# ASURA7200.net
KiCad netlist of a schematic drawn in EAGLE
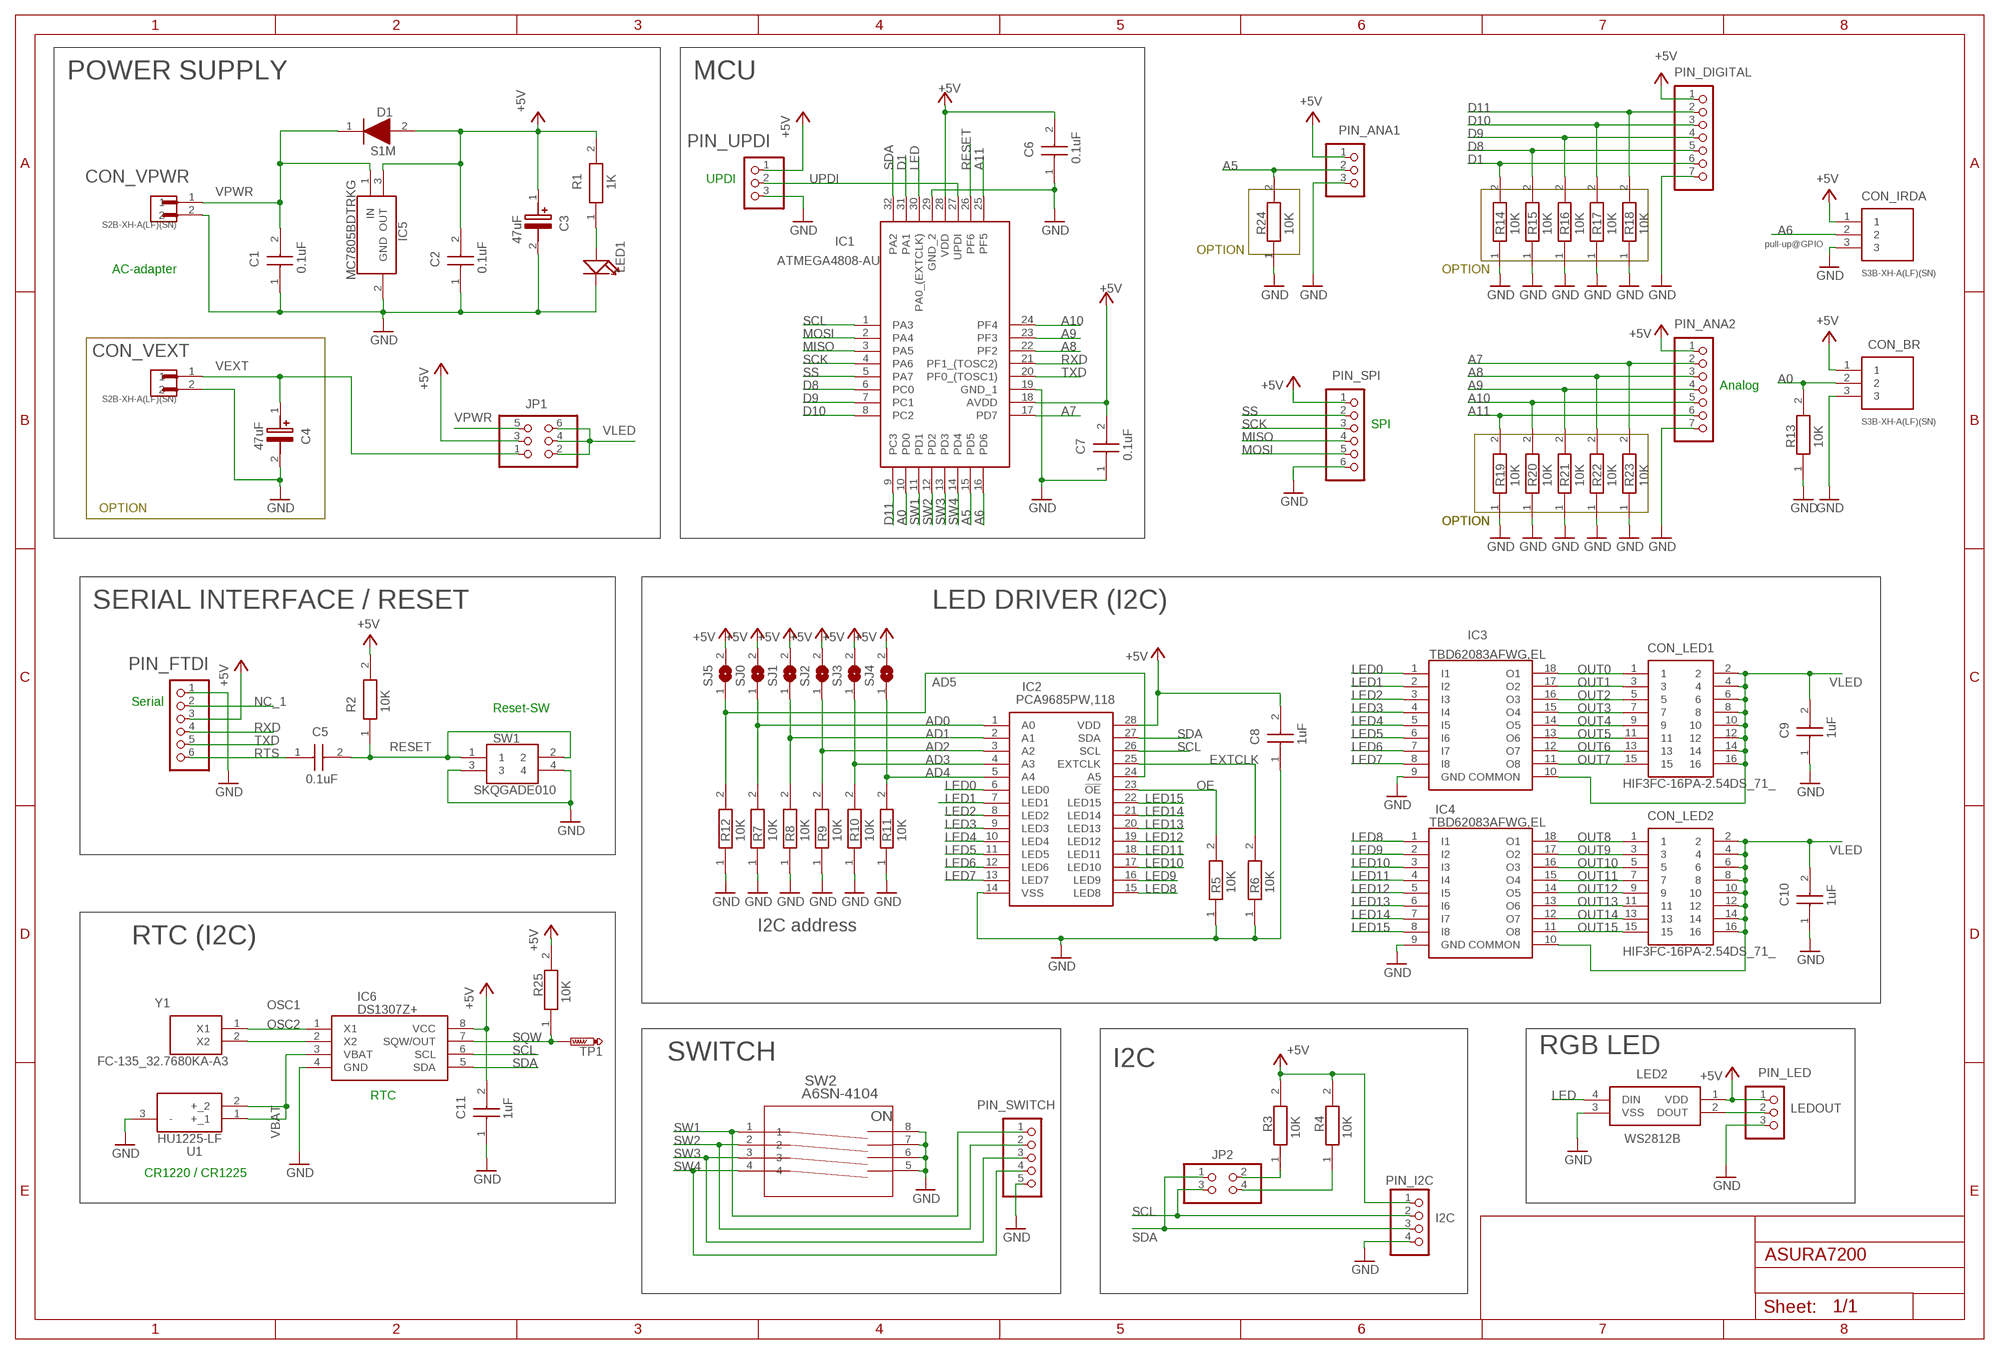
[diagram p0: schematic, sheet 1]

(export (version "E")
  (design (tool "Eeschema 10.0.6"))
  (components
    (comp (ref "C1")
      (value "CC0603KRX7R9BB104")
      (footprint "eagle-import:CAPC1608X90N")
      (fields (field (name "MOUSER_PART_NUMBER") "603-CC603KRX7R9BB104") (field (name "C") "0.1uF"))
      (libsource (lib "eagle-import") (part "CC0603KRX7R9BB104_31382856_CC0603KRX7R9BB104"))
    )
    (comp (ref "C2")
      (value "CC0603KRX7R8BB105")
      (footprint "eagle-import:CAPC1608X90N")
      (fields (field (name "MOUSER_PART_NUMBER") "603-CC603KRX7R8BB105") (field (name "C") "0.1uF"))
      (libsource (lib "eagle-import") (part "CC0603KRX7R8BB105"))
    )
    (comp (ref "C3")
      (value "UUD1H470MCL1GS")
      (footprint "eagle-import:CAPAE660X800N")
      (fields (field (name "RS_PART_NUMBER") "1677902") (field (name "C") "47uF"))
      (libsource (lib "eagle-import") (part "UUD1H470MCL1GS"))
    )
    (comp (ref "C4")
      (value "UUD1H470MCL1GS")
      (footprint "eagle-import:CAPAE660X800N")
      (fields (field (name "RS_PART_NUMBER") "1677902") (field (name "C") "47uF"))
      (libsource (lib "eagle-import") (part "UUD1H470MCL1GS"))
    )
    (comp (ref "C5")
      (value "CC0603KRX7R8BB105")
      (footprint "eagle-import:CAPC1608X90N")
      (fields (field (name "MOUSER_PART_NUMBER") "603-CC603KRX7R8BB105") (field (name "C") "0.1uF"))
      (libsource (lib "eagle-import") (part "CC0603KRX7R8BB105"))
    )
    (comp (ref "C6")
      (value "CC0603KRX7R8BB105")
      (footprint "eagle-import:CAPC1608X90N")
      (fields (field (name "MOUSER_PART_NUMBER") "603-CC603KRX7R8BB105") (field (name "C") "0.1uF"))
      (libsource (lib "eagle-import") (part "CC0603KRX7R8BB105"))
    )
    (comp (ref "C7")
      (value "CC0603KRX7R8BB105")
      (footprint "eagle-import:CAPC1608X90N")
      (fields (field (name "MOUSER_PART_NUMBER") "603-CC603KRX7R8BB105") (field (name "C") "0.1uF"))
      (libsource (lib "eagle-import") (part "CC0603KRX7R8BB105"))
    )
    (comp (ref "C8")
      (value "CC0603KRX7R9BB104")
      (footprint "eagle-import:CAPC1608X90N")
      (fields (field (name "MOUSER_PART_NUMBER") "603-CC603KRX7R9BB104") (field (name "C") "1uF"))
      (libsource (lib "eagle-import") (part "CC0603KRX7R9BB104"))
    )
    (comp (ref "C9")
      (value "CC0603KRX7R9BB104")
      (footprint "eagle-import:CAPC1608X90N")
      (fields (field (name "MOUSER_PART_NUMBER") "603-CC603KRX7R9BB104") (field (name "C") "1uF"))
      (libsource (lib "eagle-import") (part "CC0603KRX7R9BB104"))
    )
    (comp (ref "C10")
      (value "CC0603KRX7R9BB104")
      (footprint "eagle-import:CAPC1608X90N")
      (fields (field (name "MOUSER_PART_NUMBER") "603-CC603KRX7R9BB104") (field (name "C") "1uF"))
      (libsource (lib "eagle-import") (part "CC0603KRX7R9BB104"))
    )
    (comp (ref "C11")
      (value "CC0603KRX7R8BB105")
      (footprint "eagle-import:CAPC1608X90N")
      (fields (field (name "MOUSER_PART_NUMBER") "603-CC603KRX7R8BB105") (field (name "C") "1uF"))
      (libsource (lib "eagle-import") (part "CC0603KRX7R8BB105"))
    )
    (comp (ref "CON_BR")
      (value "S3B-XH-A(LF)(SN)")
      (footprint "eagle-import:JST_S3B-XH-A(LF)(SN)")
      (fields (field (name "DIGI-KEY_PART_NUMBER") "455-2250-ND") (field (name "MF") "JST Sales"))
      (libsource (lib "eagle-import") (part "S3B-XH-A(LF)(SN)"))
    )
    (comp (ref "CON_IRDA")
      (value "S3B-XH-A(LF)(SN)")
      (footprint "eagle-import:JST_S3B-XH-A(LF)(SN)")
      (fields (field (name "DIGI-KEY_PART_NUMBER") "455-2250-ND") (field (name "MF") "JST Sales"))
      (libsource (lib "eagle-import") (part "S3B-XH-A(LF)(SN)"))
    )
    (comp (ref "CON_LED1")
      (value "HIF3FC-16PA-2.54DS_71_")
      (footprint "eagle-import:SHDRRA16W69P254X254_2X8_2782X8")
      (fields
        (field (name "MANUFACTURER_PART_NUMBER") "HIF3FC-16PA-2.54DS(71)")
        (field (name "MOUSER_PART_NUMBER") "798-HIF3FC16PA254DS1")
      )
      (libsource (lib "eagle-import") (part "HIF3FC-16PA-2.54DS_71_"))
    )
    (comp (ref "CON_LED2")
      (value "HIF3FC-16PA-2.54DS_71_")
      (footprint "eagle-import:SHDRRA16W69P254X254_2X8_2782X8")
      (fields
        (field (name "MANUFACTURER_PART_NUMBER") "HIF3FC-16PA-2.54DS(71)")
        (field (name "MOUSER_PART_NUMBER") "798-HIF3FC16PA254DS1")
      )
      (libsource (lib "eagle-import") (part "HIF3FC-16PA-2.54DS_71_"))
    )
    (comp (ref "CON_VEXT")
      (value "S2B-XH-A(LF)(SN)")
      (footprint "eagle-import:JST_S2B-XH-A(LF)(SN)")
      (fields (field (name "MF") "JST Sales"))
      (libsource (lib "eagle-import") (part "S2B-XH-A(LF)(SN)"))
    )
    (comp (ref "CON_VPWR")
      (value "S2B-XH-A(LF)(SN)")
      (footprint "eagle-import:JST_S2B-XH-A(LF)(SN)")
      (fields (field (name "MF") "JST Sales"))
      (libsource (lib "eagle-import") (part "S2B-XH-A(LF)(SN)"))
    )
    (comp (ref "D1")
      (value "S1M")
      (footprint "eagle-import:DIOM5227X270N")
      (fields (field (name "RS_PART_NUMBER") "6708836"))
      (libsource (lib "eagle-import") (part "S1M"))
    )
    (comp (ref "IC1")
      (value "ATMEGA4808-AU")
      (footprint "eagle-import:QFP80P900X900X120-32N")
      (fields (field (name "MOUSER_PART_NUMBER") "556-ATMEGA4808-AU"))
      (libsource (lib "eagle-import") (part "ATMEGA4808-AU"))
    )
    (comp (ref "IC2")
      (value "PCA9685PW,118")
      (footprint "eagle-import:SOP65P640X110-28N")
      (fields (field (name "MOUSER_PART_NUMBER") "771-PCA9685PW,118"))
      (libsource (lib "eagle-import") (part "PCA9685PW,118"))
    )
    (comp (ref "IC3")
      (value "TBD62083AFWG,EL")
      (footprint "eagle-import:SOIC127P1032X285-18N")
      (fields (field (name "MOUSER_PART_NUMBER") "757-TBD62083AFWGEL"))
      (libsource (lib "eagle-import") (part "TBD62083AFWG,EL"))
    )
    (comp (ref "IC4")
      (value "TBD62083AFWG,EL")
      (footprint "eagle-import:SOIC127P1032X285-18N")
      (fields (field (name "MOUSER_PART_NUMBER") "757-TBD62083AFWGEL"))
      (libsource (lib "eagle-import") (part "TBD62083AFWG,EL"))
    )
    (comp (ref "IC5")
      (value "MC7805BDTRKG")
      (footprint "eagle-import:LM317MADTRKG")
      (fields (field (name "MOUSER_PART_NUMBER") "863-MC7805BDTRKG"))
      (libsource (lib "eagle-import") (part "MC7805BDTRKG"))
    )
    (comp (ref "IC6")
      (value "DS1307Z+")
      (footprint "eagle-import:SOIC127P600X175-8N")
      (fields (field (name "MOUSER_PART_NUMBER") "700-DS1307Z"))
      (libsource (lib "eagle-import") (part "DS1307Z+"))
    )
    (comp (ref "JP1")
      (value "PINHD-2X3")
      (footprint "eagle-import:2X03")
      (libsource (lib "eagle-import") (part "PINHD-2X3"))
    )
    (comp (ref "JP2")
      (value "PINHD-2X2")
      (footprint "eagle-import:2X02")
      (libsource (lib "eagle-import") (part "PINHD-2X2"))
    )
    (comp (ref "LED1")
      (value "SMD-LED-CLEAR-GREEN(0603)")
      (footprint "eagle-import:LED-0603")
      (fields (field (name "MF") "Everlight") (field (name "MP") "19-217/G7C-AN1P2/3T"))
      (libsource (lib "eagle-import") (part "SMD-LED-CLEAR-GREEN(0603)"))
    )
    (comp (ref "LED2")
      (value "WS2812B")
      (footprint "eagle-import:WS2812B")
      (libsource (lib "eagle-import") (part "WS2812B"))
    )
    (comp (ref "PIN_ANA1")
      (value "PINHD-1X3")
      (footprint "eagle-import:1X03")
      (libsource (lib "eagle-import") (part "PINHD-1X3"))
    )
    (comp (ref "PIN_ANA2")
      (value "PINHD-1X7")
      (footprint "eagle-import:1X07")
      (libsource (lib "eagle-import") (part "PINHD-1X7"))
    )
    (comp (ref "PIN_DIGITAL")
      (value "PINHD-1X7")
      (footprint "eagle-import:1X07")
      (libsource (lib "eagle-import") (part "PINHD-1X7"))
    )
    (comp (ref "PIN_FTDI")
      (value "PINHD-1X6/90")
      (footprint "eagle-import:1X06_90")
      (libsource (lib "eagle-import") (part "PINHD-1X6/90"))
    )
    (comp (ref "PIN_I2C")
      (value "PINHD-1X4")
      (footprint "eagle-import:1X04")
      (libsource (lib "eagle-import") (part "PINHD-1X4"))
    )
    (comp (ref "PIN_LED")
      (value "PINHD-1X3")
      (footprint "eagle-import:1X03")
      (libsource (lib "eagle-import") (part "PINHD-1X3"))
    )
    (comp (ref "PIN_SPI")
      (value "PINHD-1X6")
      (footprint "eagle-import:1X06")
      (libsource (lib "eagle-import") (part "PINHD-1X6"))
    )
    (comp (ref "PIN_SWITCH")
      (value "PINHD-1X5")
      (footprint "eagle-import:1X05")
      (libsource (lib "eagle-import") (part "PINHD-1X5"))
    )
    (comp (ref "PIN_UPDI")
      (value "PINHD-1X3")
      (footprint "eagle-import:1X03")
      (libsource (lib "eagle-import") (part "PINHD-1X3"))
    )
    (comp (ref "R1")
      (value "RC0603JR-071KL")
      (footprint "eagle-import:RESC1608X55N")
      (fields (field (name "MOUSER_PART_NUMBER") "603-RC0603JR-071KL") (field (name "R") "1K"))
      (libsource (lib "eagle-import") (part "RC0603JR-071KL"))
    )
    (comp (ref "R2")
      (value "RC0603JR-0710KL")
      (footprint "eagle-import:RESC1608X55N")
      (fields (field (name "MOUSER_PART_NUMBER") "603-RC0603JR-0710KL") (field (name "R") "10K"))
      (libsource (lib "eagle-import") (part "RC0603JR-0710KL"))
    )
    (comp (ref "R3")
      (value "RC0603JR-0710KL")
      (footprint "eagle-import:RESC1608X55N")
      (fields (field (name "MOUSER_PART_NUMBER") "603-RC0603JR-0710KL") (field (name "R") "10K"))
      (libsource (lib "eagle-import") (part "RC0603JR-0710KL"))
    )
    (comp (ref "R4")
      (value "RC0603JR-0710KL")
      (footprint "eagle-import:RESC1608X55N")
      (fields (field (name "MOUSER_PART_NUMBER") "603-RC0603JR-0710KL") (field (name "R") "10K"))
      (libsource (lib "eagle-import") (part "RC0603JR-0710KL"))
    )
    (comp (ref "R5")
      (value "RC0603JR-0710KL")
      (footprint "eagle-import:RESC1608X55N")
      (fields (field (name "MOUSER_PART_NUMBER") "603-RC0603JR-0710KL") (field (name "R") "10K"))
      (libsource (lib "eagle-import") (part "RC0603JR-0710KL"))
    )
    (comp (ref "R6")
      (value "RC0603JR-0710KL")
      (footprint "eagle-import:RESC1608X55N")
      (fields (field (name "MOUSER_PART_NUMBER") "603-RC0603JR-0710KL") (field (name "R") "10K"))
      (libsource (lib "eagle-import") (part "RC0603JR-0710KL"))
    )
    (comp (ref "R7")
      (value "RC0603JR-0710KL")
      (footprint "eagle-import:RESC1608X55N")
      (fields (field (name "MOUSER_PART_NUMBER") "603-RC0603JR-0710KL") (field (name "R") "10K"))
      (libsource (lib "eagle-import") (part "RC0603JR-0710KL"))
    )
    (comp (ref "R8")
      (value "RC0603JR-0710KL")
      (footprint "eagle-import:RESC1608X55N")
      (fields (field (name "MOUSER_PART_NUMBER") "603-RC0603JR-0710KL") (field (name "R") "10K"))
      (libsource (lib "eagle-import") (part "RC0603JR-0710KL"))
    )
    (comp (ref "R9")
      (value "RC0603JR-0710KL")
      (footprint "eagle-import:RESC1608X55N")
      (fields (field (name "MOUSER_PART_NUMBER") "603-RC0603JR-0710KL") (field (name "R") "10K"))
      (libsource (lib "eagle-import") (part "RC0603JR-0710KL"))
    )
    (comp (ref "R10")
      (value "RC0603JR-0710KL")
      (footprint "eagle-import:RESC1608X55N")
      (fields (field (name "MOUSER_PART_NUMBER") "603-RC0603JR-0710KL") (field (name "R") "10K"))
      (libsource (lib "eagle-import") (part "RC0603JR-0710KL"))
    )
    (comp (ref "R11")
      (value "RC0603JR-0710KL")
      (footprint "eagle-import:RESC1608X55N")
      (fields (field (name "MOUSER_PART_NUMBER") "603-RC0603JR-0710KL") (field (name "R") "10K"))
      (libsource (lib "eagle-import") (part "RC0603JR-0710KL"))
    )
    (comp (ref "R12")
      (value "RC0603JR-0710KL")
      (footprint "eagle-import:RESC1608X55N")
      (fields (field (name "MOUSER_PART_NUMBER") "603-RC0603JR-0710KL") (field (name "R") "10K"))
      (libsource (lib "eagle-import") (part "RC0603JR-0710KL"))
    )
    (comp (ref "R13")
      (value "RC0603JR-0710KL")
      (footprint "eagle-import:RESC1608X55N")
      (fields (field (name "MOUSER_PART_NUMBER") "603-RC0603JR-0710KL") (field (name "R") "10K"))
      (libsource (lib "eagle-import") (part "RC0603JR-0710KL"))
    )
    (comp (ref "R14")
      (value "RC0603JR-0710KL")
      (footprint "eagle-import:RESC1608X55N")
      (fields (field (name "MOUSER_PART_NUMBER") "603-RC0603JR-0710KL") (field (name "R") "10K"))
      (libsource (lib "eagle-import") (part "RC0603JR-0710KL"))
    )
    (comp (ref "R15")
      (value "RC0603JR-0710KL")
      (footprint "eagle-import:RESC1608X55N")
      (fields (field (name "MOUSER_PART_NUMBER") "603-RC0603JR-0710KL") (field (name "R") "10K"))
      (libsource (lib "eagle-import") (part "RC0603JR-0710KL"))
    )
    (comp (ref "R16")
      (value "RC0603JR-0710KL")
      (footprint "eagle-import:RESC1608X55N")
      (fields (field (name "MOUSER_PART_NUMBER") "603-RC0603JR-0710KL") (field (name "R") "10K"))
      (libsource (lib "eagle-import") (part "RC0603JR-0710KL"))
    )
    (comp (ref "R17")
      (value "RC0603JR-0710KL")
      (footprint "eagle-import:RESC1608X55N")
      (fields (field (name "MOUSER_PART_NUMBER") "603-RC0603JR-0710KL") (field (name "R") "10K"))
      (libsource (lib "eagle-import") (part "RC0603JR-0710KL"))
    )
    (comp (ref "R18")
      (value "RC0603JR-0710KL")
      (footprint "eagle-import:RESC1608X55N")
      (fields (field (name "MOUSER_PART_NUMBER") "603-RC0603JR-0710KL") (field (name "R") "10K"))
      (libsource (lib "eagle-import") (part "RC0603JR-0710KL"))
    )
    (comp (ref "R19")
      (value "RC0603JR-0710KL")
      (footprint "eagle-import:RESC1608X55N")
      (fields (field (name "MOUSER_PART_NUMBER") "603-RC0603JR-0710KL") (field (name "R") "10K"))
      (libsource (lib "eagle-import") (part "RC0603JR-0710KL"))
    )
    (comp (ref "R20")
      (value "RC0603JR-0710KL")
      (footprint "eagle-import:RESC1608X55N")
      (fields (field (name "MOUSER_PART_NUMBER") "603-RC0603JR-0710KL") (field (name "R") "10K"))
      (libsource (lib "eagle-import") (part "RC0603JR-0710KL"))
    )
    (comp (ref "R21")
      (value "RC0603JR-0710KL")
      (footprint "eagle-import:RESC1608X55N")
      (fields (field (name "MOUSER_PART_NUMBER") "603-RC0603JR-0710KL") (field (name "R") "10K"))
      (libsource (lib "eagle-import") (part "RC0603JR-0710KL"))
    )
    (comp (ref "R22")
      (value "RC0603JR-0710KL")
      (footprint "eagle-import:RESC1608X55N")
      (fields (field (name "MOUSER_PART_NUMBER") "603-RC0603JR-0710KL") (field (name "R") "10K"))
      (libsource (lib "eagle-import") (part "RC0603JR-0710KL"))
    )
    (comp (ref "R23")
      (value "RC0603JR-0710KL")
      (footprint "eagle-import:RESC1608X55N")
      (fields (field (name "MOUSER_PART_NUMBER") "603-RC0603JR-0710KL") (field (name "R") "10K"))
      (libsource (lib "eagle-import") (part "RC0603JR-0710KL"))
    )
    (comp (ref "R24")
      (value "RC0603JR-0710KL")
      (footprint "eagle-import:RESC1608X55N")
      (fields (field (name "MOUSER_PART_NUMBER") "603-RC0603JR-0710KL") (field (name "R") "10K"))
      (libsource (lib "eagle-import") (part "RC0603JR-0710KL"))
    )
    (comp (ref "R25")
      (value "RC0603JR-0710KL")
      (footprint "eagle-import:RESC1608X55N")
      (fields (field (name "MOUSER_PART_NUMBER") "603-RC0603JR-0710KL") (field (name "R") "10K"))
      (libsource (lib "eagle-import") (part "RC0603JR-0710KL"))
    )
    (comp (ref "SJ0") (value "SJ") (footprint "eagle-import:SJ") (libsource (lib "eagle-import") (part "SJ")))
    (comp (ref "SJ1") (value "SJ") (footprint "eagle-import:SJ") (libsource (lib "eagle-import") (part "SJ")))
    (comp (ref "SJ2") (value "SJ") (footprint "eagle-import:SJ") (libsource (lib "eagle-import") (part "SJ")))
    (comp (ref "SJ3") (value "SJ") (footprint "eagle-import:SJ") (libsource (lib "eagle-import") (part "SJ")))
    (comp (ref "SJ4") (value "SJ") (footprint "eagle-import:SJ") (libsource (lib "eagle-import") (part "SJ")))
    (comp (ref "SJ5") (value "SJ") (footprint "eagle-import:SJ") (libsource (lib "eagle-import") (part "SJ")))
    (comp (ref "SW1")
      (value "SKQGADE010")
      (footprint "eagle-import:SKQGAKE010")
      (fields (field (name "MOUSER_PART_NUMBER") "688-SKQGAD"))
      (libsource (lib "eagle-import") (part "SKQGADE010"))
    )
    (comp (ref "SW2")
      (value "A6SN-4104")
      (footprint "eagle-import:SW_A6SN-4104_OMR")
      (fields (field (name "COPYRIGHT") "Copyright (C) 2018 Accelerated Designs. All rights reserved"))
      (libsource (lib "eagle-import") (part "A6SN-4104"))
    )
    (comp (ref "TP1")
      (value "PTR1PAD1-13")
      (footprint "eagle-import:P1-13")
      (libsource (lib "eagle-import") (part "PTR1PAD1-13"))
    )
    (comp (ref "U1")
      (value "HU1225-LF")
      (footprint "eagle-import:HU1225LF")
      (fields (field (name "MOUSER_PART_NUMBER") "614-HU1225-LF"))
      (libsource (lib "eagle-import") (part "HU1225-LF"))
    )
    (comp (ref "Y1")
      (value "FC-135_32.7680KA-A3")
      (footprint "eagle-import:FC135327680KAA3")
      (fields
        (field (name "MANUFACTURER_PART_NUMBER") "FC-135 32.7680KA-A3")
        (field (name "MOUSER_PART_NUMBER") "732-FC135-32.76KAA3")
      )
      (libsource (lib "eagle-import") (part "FC-135_32.7680KA-A3"))
    )
  )
  (nets
    (net (code "1") (name "+5V") (class "Default")
      (node (ref "C11") (pin "2") (pinfunction "2_2") (pintype "bidirectional"))
      (node (ref "C2") (pin "2") (pinfunction "2_2") (pintype "bidirectional"))
      (node (ref "C3") (pin "1") (pinfunction "+_1") (pintype "bidirectional"))
      (node (ref "C6") (pin "2") (pinfunction "2_2") (pintype "bidirectional"))
      (node (ref "C7") (pin "2") (pinfunction "2_2") (pintype "bidirectional"))
      (node (ref "C8") (pin "2") (pinfunction "2_2") (pintype "bidirectional"))
      (node (ref "CON_BR") (pin "1") (pinfunction "1_1") (pintype "passive"))
      (node (ref "CON_IRDA") (pin "1") (pinfunction "1_1") (pintype "passive"))
      (node (ref "D1") (pin "2") (pinfunction "A_2") (pintype "bidirectional"))
      (node (ref "IC1") (pin "18") (pinfunction "AVDD_18") (pintype "bidirectional"))
      (node (ref "IC1") (pin "28") (pinfunction "VDD_28") (pintype "bidirectional"))
      (node (ref "IC2") (pin "28") (pinfunction "VDD_28") (pintype "bidirectional"))
      (node (ref "IC5") (pin "3") (pinfunction "OUT_3") (pintype "bidirectional"))
      (node (ref "IC6") (pin "8") (pinfunction "VCC_8") (pintype "bidirectional"))
      (node (ref "JP1") (pin "3") (pinfunction "3_3") (pintype "passive"))
      (node (ref "LED2") (pin "1") (pinfunction "VDD_1") (pintype "power_in"))
      (node (ref "PIN_ANA1") (pin "1") (pinfunction "1_1") (pintype "passive"))
      (node (ref "PIN_ANA2") (pin "1") (pinfunction "1_1") (pintype "passive"))
      (node (ref "PIN_DIGITAL") (pin "1") (pinfunction "1_1") (pintype "passive"))
      (node (ref "PIN_FTDI") (pin "3") (pinfunction "3_3") (pintype "passive"))
      (node (ref "PIN_I2C") (pin "1") (pinfunction "1_1") (pintype "passive"))
      (node (ref "PIN_LED") (pin "1") (pinfunction "1_1") (pintype "passive"))
      (node (ref "PIN_SPI") (pin "1") (pinfunction "1_1") (pintype "passive"))
      (node (ref "PIN_UPDI") (pin "1") (pinfunction "1_1") (pintype "passive"))
      (node (ref "R1") (pin "2") (pinfunction "2_2") (pintype "bidirectional"))
      (node (ref "R2") (pin "2") (pinfunction "2_2") (pintype "bidirectional"))
      (node (ref "R25") (pin "2") (pinfunction "2_2") (pintype "bidirectional"))
      (node (ref "R3") (pin "2") (pinfunction "2_2") (pintype "bidirectional"))
      (node (ref "R4") (pin "2") (pinfunction "2_2") (pintype "bidirectional"))
      (node (ref "SJ0") (pin "2") (pinfunction "2_2") (pintype "passive"))
      (node (ref "SJ1") (pin "2") (pinfunction "2_2") (pintype "passive"))
      (node (ref "SJ2") (pin "2") (pinfunction "2_2") (pintype "passive"))
      (node (ref "SJ3") (pin "2") (pinfunction "2_2") (pintype "passive"))
      (node (ref "SJ4") (pin "2") (pinfunction "2_2") (pintype "passive"))
      (node (ref "SJ5") (pin "2") (pinfunction "2_2") (pintype "passive"))
    )
    (net (code "2") (name "/A0") (class "Default")
      (node (ref "CON_BR") (pin "2") (pinfunction "2_2") (pintype "passive"))
      (node (ref "IC1") (pin "10") (pinfunction "PD0_10") (pintype "bidirectional"))
      (node (ref "R13") (pin "2") (pinfunction "2_2") (pintype "bidirectional"))
    )
    (net (code "3") (name "/A5") (class "Default")
      (node (ref "IC1") (pin "15") (pinfunction "PD5_15") (pintype "bidirectional"))
      (node (ref "PIN_ANA1") (pin "2") (pinfunction "2_2") (pintype "passive"))
      (node (ref "R24") (pin "2") (pinfunction "2_2") (pintype "bidirectional"))
    )
    (net (code "4") (name "/A6") (class "Default")
      (node (ref "CON_IRDA") (pin "2") (pinfunction "2_2") (pintype "passive"))
      (node (ref "IC1") (pin "16") (pinfunction "PD6_16") (pintype "bidirectional"))
    )
    (net (code "5") (name "/A7") (class "Default")
      (node (ref "IC1") (pin "17") (pinfunction "PD7_17") (pintype "bidirectional"))
      (node (ref "PIN_ANA2") (pin "2") (pinfunction "2_2") (pintype "passive"))
      (node (ref "R23") (pin "2") (pinfunction "2_2") (pintype "bidirectional"))
    )
    (net (code "6") (name "/A8") (class "Default")
      (node (ref "IC1") (pin "22") (pinfunction "PF2_22") (pintype "bidirectional"))
      (node (ref "PIN_ANA2") (pin "3") (pinfunction "3_3") (pintype "passive"))
      (node (ref "R22") (pin "2") (pinfunction "2_2") (pintype "bidirectional"))
    )
    (net (code "7") (name "/A9") (class "Default")
      (node (ref "IC1") (pin "23") (pinfunction "PF3_23") (pintype "bidirectional"))
      (node (ref "PIN_ANA2") (pin "4") (pinfunction "4_4") (pintype "passive"))
      (node (ref "R21") (pin "2") (pinfunction "2_2") (pintype "bidirectional"))
    )
    (net (code "8") (name "/A10") (class "Default")
      (node (ref "IC1") (pin "24") (pinfunction "PF4_24") (pintype "bidirectional"))
      (node (ref "PIN_ANA2") (pin "5") (pinfunction "5_5") (pintype "passive"))
      (node (ref "R20") (pin "2") (pinfunction "2_2") (pintype "bidirectional"))
    )
    (net (code "9") (name "/A11") (class "Default")
      (node (ref "IC1") (pin "25") (pinfunction "PF5_25") (pintype "bidirectional"))
      (node (ref "PIN_ANA2") (pin "6") (pinfunction "6_6") (pintype "passive"))
      (node (ref "R19") (pin "2") (pinfunction "2_2") (pintype "bidirectional"))
    )
    (net (code "10") (name "/AD0") (class "Default")
      (node (ref "IC2") (pin "1") (pinfunction "A0_1") (pintype "bidirectional"))
      (node (ref "R7") (pin "2") (pinfunction "2_2") (pintype "bidirectional"))
      (node (ref "SJ0") (pin "1") (pinfunction "1_1") (pintype "passive"))
    )
    (net (code "11") (name "/AD1") (class "Default")
      (node (ref "IC2") (pin "2") (pinfunction "A1_2") (pintype "bidirectional"))
      (node (ref "R8") (pin "2") (pinfunction "2_2") (pintype "bidirectional"))
      (node (ref "SJ1") (pin "1") (pinfunction "1_1") (pintype "passive"))
    )
    (net (code "12") (name "/AD2") (class "Default")
      (node (ref "IC2") (pin "3") (pinfunction "A2_3") (pintype "bidirectional"))
      (node (ref "R9") (pin "2") (pinfunction "2_2") (pintype "bidirectional"))
      (node (ref "SJ2") (pin "1") (pinfunction "1_1") (pintype "passive"))
    )
    (net (code "13") (name "/AD3") (class "Default")
      (node (ref "IC2") (pin "4") (pinfunction "A3_4") (pintype "bidirectional"))
      (node (ref "R10") (pin "2") (pinfunction "2_2") (pintype "bidirectional"))
      (node (ref "SJ3") (pin "1") (pinfunction "1_1") (pintype "passive"))
    )
    (net (code "14") (name "/AD4") (class "Default")
      (node (ref "IC2") (pin "5") (pinfunction "A4_5") (pintype "bidirectional"))
      (node (ref "R11") (pin "2") (pinfunction "2_2") (pintype "bidirectional"))
      (node (ref "SJ4") (pin "1") (pinfunction "1_1") (pintype "passive"))
    )
    (net (code "15") (name "/AD5") (class "Default")
      (node (ref "IC2") (pin "24") (pinfunction "A5_24") (pintype "bidirectional"))
      (node (ref "R12") (pin "2") (pinfunction "2_2") (pintype "bidirectional"))
      (node (ref "SJ5") (pin "1") (pinfunction "1_1") (pintype "passive"))
    )
    (net (code "16") (name "/D1") (class "Default")
      (node (ref "IC1") (pin "31") (pinfunction "PA1_31") (pintype "bidirectional"))
      (node (ref "PIN_DIGITAL") (pin "6") (pinfunction "6_6") (pintype "passive"))
      (node (ref "R14") (pin "2") (pinfunction "2_2") (pintype "bidirectional"))
    )
    (net (code "17") (name "/D8") (class "Default")
      (node (ref "IC1") (pin "6") (pinfunction "PC0_6") (pintype "bidirectional"))
      (node (ref "PIN_DIGITAL") (pin "5") (pinfunction "5_5") (pintype "passive"))
      (node (ref "R15") (pin "2") (pinfunction "2_2") (pintype "bidirectional"))
    )
    (net (code "18") (name "/D9") (class "Default")
      (node (ref "IC1") (pin "7") (pinfunction "PC1_7") (pintype "bidirectional"))
      (node (ref "PIN_DIGITAL") (pin "4") (pinfunction "4_4") (pintype "passive"))
      (node (ref "R16") (pin "2") (pinfunction "2_2") (pintype "bidirectional"))
    )
    (net (code "19") (name "/D10") (class "Default")
      (node (ref "IC1") (pin "8") (pinfunction "PC2_8") (pintype "bidirectional"))
      (node (ref "PIN_DIGITAL") (pin "3") (pinfunction "3_3") (pintype "passive"))
      (node (ref "R17") (pin "2") (pinfunction "2_2") (pintype "bidirectional"))
    )
    (net (code "20") (name "/D11") (class "Default")
      (node (ref "IC1") (pin "9") (pinfunction "PC3_9") (pintype "bidirectional"))
      (node (ref "PIN_DIGITAL") (pin "2") (pinfunction "2_2") (pintype "passive"))
      (node (ref "R18") (pin "2") (pinfunction "2_2") (pintype "bidirectional"))
    )
    (net (code "21") (name "/EXTCLK") (class "Default")
      (node (ref "IC2") (pin "25") (pinfunction "EXTCLK_25") (pintype "bidirectional"))
      (node (ref "R6") (pin "2") (pinfunction "2_2") (pintype "bidirectional"))
    )
    (net (code "22") (name "/LED") (class "Default")
      (node (ref "IC1") (pin "30") (pinfunction "PA0_(EXTCLK)_30") (pintype "bidirectional"))
      (node (ref "LED2") (pin "4") (pinfunction "DIN_4") (pintype "input"))
    )
    (net (code "23") (name "/LED0") (class "Default")
      (node (ref "IC2") (pin "6") (pinfunction "LED0_6") (pintype "bidirectional"))
      (node (ref "IC3") (pin "1") (pinfunction "I1_1") (pintype "bidirectional"))
    )
    (net (code "24") (name "/LED1") (class "Default")
      (node (ref "IC2") (pin "7") (pinfunction "LED1_7") (pintype "bidirectional"))
      (node (ref "IC3") (pin "2") (pinfunction "I2_2") (pintype "bidirectional"))
    )
    (net (code "25") (name "/LED2") (class "Default")
      (node (ref "IC2") (pin "8") (pinfunction "LED2_8") (pintype "bidirectional"))
      (node (ref "IC3") (pin "3") (pinfunction "I3_3") (pintype "bidirectional"))
    )
    (net (code "26") (name "/LED3") (class "Default")
      (node (ref "IC2") (pin "9") (pinfunction "LED3_9") (pintype "bidirectional"))
      (node (ref "IC3") (pin "4") (pinfunction "I4_4") (pintype "bidirectional"))
    )
    (net (code "27") (name "/LED4") (class "Default")
      (node (ref "IC2") (pin "10") (pinfunction "LED4_10") (pintype "bidirectional"))
      (node (ref "IC3") (pin "5") (pinfunction "I5_5") (pintype "bidirectional"))
    )
    (net (code "28") (name "/LED5") (class "Default")
      (node (ref "IC2") (pin "11") (pinfunction "LED5_11") (pintype "bidirectional"))
      (node (ref "IC3") (pin "6") (pinfunction "I6_6") (pintype "bidirectional"))
    )
    (net (code "29") (name "/LED6") (class "Default")
      (node (ref "IC2") (pin "12") (pinfunction "LED6_12") (pintype "bidirectional"))
      (node (ref "IC3") (pin "7") (pinfunction "I7_7") (pintype "bidirectional"))
    )
    (net (code "30") (name "/LED7") (class "Default")
      (node (ref "IC2") (pin "13") (pinfunction "LED7_13") (pintype "bidirectional"))
      (node (ref "IC3") (pin "8") (pinfunction "I8_8") (pintype "bidirectional"))
    )
    (net (code "31") (name "/LED8") (class "Default")
      (node (ref "IC2") (pin "15") (pinfunction "LED8_15") (pintype "bidirectional"))
      (node (ref "IC4") (pin "1") (pinfunction "I1_1") (pintype "bidirectional"))
    )
    (net (code "32") (name "/LED9") (class "Default")
      (node (ref "IC2") (pin "16") (pinfunction "LED9_16") (pintype "bidirectional"))
      (node (ref "IC4") (pin "2") (pinfunction "I2_2") (pintype "bidirectional"))
    )
    (net (code "33") (name "/LED10") (class "Default")
      (node (ref "IC2") (pin "17") (pinfunction "LED10_17") (pintype "bidirectional"))
      (node (ref "IC4") (pin "3") (pinfunction "I3_3") (pintype "bidirectional"))
    )
    (net (code "34") (name "/LED11") (class "Default")
      (node (ref "IC2") (pin "18") (pinfunction "LED11_18") (pintype "bidirectional"))
      (node (ref "IC4") (pin "4") (pinfunction "I4_4") (pintype "bidirectional"))
    )
    (net (code "35") (name "/LED12") (class "Default")
      (node (ref "IC2") (pin "19") (pinfunction "LED12_19") (pintype "bidirectional"))
      (node (ref "IC4") (pin "5") (pinfunction "I5_5") (pintype "bidirectional"))
    )
    (net (code "36") (name "/LED13") (class "Default")
      (node (ref "IC2") (pin "20") (pinfunction "LED13_20") (pintype "bidirectional"))
      (node (ref "IC4") (pin "6") (pinfunction "I6_6") (pintype "bidirectional"))
    )
    (net (code "37") (name "/LED14") (class "Default")
      (node (ref "IC2") (pin "21") (pinfunction "LED14_21") (pintype "bidirectional"))
      (node (ref "IC4") (pin "7") (pinfunction "I7_7") (pintype "bidirectional"))
    )
    (net (code "38") (name "/LED15") (class "Default")
      (node (ref "IC2") (pin "22") (pinfunction "LED15_22") (pintype "bidirectional"))
      (node (ref "IC4") (pin "8") (pinfunction "I8_8") (pintype "bidirectional"))
    )
    (net (code "39") (name "/LEDOUT") (class "Default")
      (node (ref "LED2") (pin "2") (pinfunction "DOUT_2") (pintype "output"))
      (node (ref "PIN_LED") (pin "2") (pinfunction "2_2") (pintype "passive"))
    )
    (net (code "40") (name "/MISO") (class "Default")
      (node (ref "IC1") (pin "3") (pinfunction "PA5_3") (pintype "bidirectional"))
      (node (ref "PIN_SPI") (pin "4") (pinfunction "4_4") (pintype "passive"))
    )
    (net (code "41") (name "/MOSI") (class "Default")
      (node (ref "IC1") (pin "2") (pinfunction "PA4_2") (pintype "bidirectional"))
      (node (ref "PIN_SPI") (pin "5") (pinfunction "5_5") (pintype "passive"))
    )
    (net (code "42") (name "/NC_1") (class "Default")
      (node (ref "PIN_FTDI") (pin "2") (pinfunction "2_2") (pintype "passive"))
    )
    (net (code "43") (name "/OE") (class "Default")
      (node (ref "IC2") (pin "23") (pinfunction "~{OE}_23") (pintype "bidirectional"))
      (node (ref "R5") (pin "2") (pinfunction "2_2") (pintype "bidirectional"))
    )
    (net (code "44") (name "/OSC1") (class "Default")
      (node (ref "IC6") (pin "1") (pinfunction "X1_1") (pintype "bidirectional"))
      (node (ref "Y1") (pin "1") (pinfunction "X1_1") (pintype "bidirectional"))
    )
    (net (code "45") (name "/OSC2") (class "Default")
      (node (ref "IC6") (pin "2") (pinfunction "X2_2") (pintype "bidirectional"))
      (node (ref "Y1") (pin "2") (pinfunction "X2_2") (pintype "bidirectional"))
    )
    (net (code "46") (name "/OUT0") (class "Default")
      (node (ref "CON_LED1") (pin "1") (pinfunction "1_1") (pintype "bidirectional"))
      (node (ref "IC3") (pin "18") (pinfunction "O1_18") (pintype "bidirectional"))
    )
    (net (code "47") (name "/OUT1") (class "Default")
      (node (ref "CON_LED1") (pin "3") (pinfunction "3_3") (pintype "bidirectional"))
      (node (ref "IC3") (pin "17") (pinfunction "O2_17") (pintype "bidirectional"))
    )
    (net (code "48") (name "/OUT2") (class "Default")
      (node (ref "CON_LED1") (pin "5") (pinfunction "5_5") (pintype "bidirectional"))
      (node (ref "IC3") (pin "16") (pinfunction "O3_16") (pintype "bidirectional"))
    )
    (net (code "49") (name "/OUT3") (class "Default")
      (node (ref "CON_LED1") (pin "7") (pinfunction "7_7") (pintype "bidirectional"))
      (node (ref "IC3") (pin "15") (pinfunction "O4_15") (pintype "bidirectional"))
    )
    (net (code "50") (name "/OUT4") (class "Default")
      (node (ref "CON_LED1") (pin "9") (pinfunction "9_9") (pintype "bidirectional"))
      (node (ref "IC3") (pin "14") (pinfunction "O5_14") (pintype "bidirectional"))
    )
    (net (code "51") (name "/OUT5") (class "Default")
      (node (ref "CON_LED1") (pin "11") (pinfunction "11_11") (pintype "bidirectional"))
      (node (ref "IC3") (pin "13") (pinfunction "O6_13") (pintype "bidirectional"))
    )
    (net (code "52") (name "/OUT6") (class "Default")
      (node (ref "CON_LED1") (pin "13") (pinfunction "13_13") (pintype "bidirectional"))
      (node (ref "IC3") (pin "12") (pinfunction "O7_12") (pintype "bidirectional"))
    )
    (net (code "53") (name "/OUT7") (class "Default")
      (node (ref "CON_LED1") (pin "15") (pinfunction "15_15") (pintype "bidirectional"))
      (node (ref "IC3") (pin "11") (pinfunction "O8_11") (pintype "bidirectional"))
    )
    (net (code "54") (name "/OUT8") (class "Default")
      (node (ref "CON_LED2") (pin "1") (pinfunction "1_1") (pintype "bidirectional"))
      (node (ref "IC4") (pin "18") (pinfunction "O1_18") (pintype "bidirectional"))
    )
    (net (code "55") (name "/OUT9") (class "Default")
      (node (ref "CON_LED2") (pin "3") (pinfunction "3_3") (pintype "bidirectional"))
      (node (ref "IC4") (pin "17") (pinfunction "O2_17") (pintype "bidirectional"))
    )
    (net (code "56") (name "/OUT10") (class "Default")
      (node (ref "CON_LED2") (pin "5") (pinfunction "5_5") (pintype "bidirectional"))
      (node (ref "IC4") (pin "16") (pinfunction "O3_16") (pintype "bidirectional"))
    )
    (net (code "57") (name "/OUT11") (class "Default")
      (node (ref "CON_LED2") (pin "7") (pinfunction "7_7") (pintype "bidirectional"))
      (node (ref "IC4") (pin "15") (pinfunction "O4_15") (pintype "bidirectional"))
    )
    (net (code "58") (name "/OUT12") (class "Default")
      (node (ref "CON_LED2") (pin "9") (pinfunction "9_9") (pintype "bidirectional"))
      (node (ref "IC4") (pin "14") (pinfunction "O5_14") (pintype "bidirectional"))
    )
    (net (code "59") (name "/OUT13") (class "Default")
      (node (ref "CON_LED2") (pin "11") (pinfunction "11_11") (pintype "bidirectional"))
      (node (ref "IC4") (pin "13") (pinfunction "O6_13") (pintype "bidirectional"))
    )
    (net (code "60") (name "/OUT14") (class "Default")
      (node (ref "CON_LED2") (pin "13") (pinfunction "13_13") (pintype "bidirectional"))
      (node (ref "IC4") (pin "12") (pinfunction "O7_12") (pintype "bidirectional"))
    )
    (net (code "61") (name "/OUT15") (class "Default")
      (node (ref "CON_LED2") (pin "15") (pinfunction "15_15") (pintype "bidirectional"))
      (node (ref "IC4") (pin "11") (pinfunction "O8_11") (pintype "bidirectional"))
    )
    (net (code "62") (name "/RESET") (class "Default")
      (node (ref "C5") (pin "2") (pinfunction "2_2") (pintype "bidirectional"))
      (node (ref "IC1") (pin "26") (pinfunction "PF6_26") (pintype "bidirectional"))
      (node (ref "R2") (pin "1") (pinfunction "1_1") (pintype "bidirectional"))
      (node (ref "SW1") (pin "1") (pinfunction "1_1") (pintype "bidirectional"))
      (node (ref "SW1") (pin "2") (pinfunction "2_2") (pintype "bidirectional"))
    )
    (net (code "63") (name "/RTS") (class "Default")
      (node (ref "C5") (pin "1") (pinfunction "1_1") (pintype "bidirectional"))
      (node (ref "PIN_FTDI") (pin "6") (pinfunction "6_6") (pintype "passive"))
    )
    (net (code "64") (name "/RXD") (class "Default")
      (node (ref "IC1") (pin "21") (pinfunction "PF1_(TOSC2)_21") (pintype "bidirectional"))
      (node (ref "PIN_FTDI") (pin "4") (pinfunction "4_4") (pintype "passive"))
    )
    (net (code "65") (name "/SCK") (class "Default")
      (node (ref "IC1") (pin "4") (pinfunction "PA6_4") (pintype "bidirectional"))
      (node (ref "PIN_SPI") (pin "3") (pinfunction "3_3") (pintype "passive"))
    )
    (net (code "66") (name "/SCL") (class "Default")
      (node (ref "IC1") (pin "1") (pinfunction "PA3_1") (pintype "bidirectional"))
      (node (ref "IC2") (pin "26") (pinfunction "SCL_26") (pintype "bidirectional"))
      (node (ref "IC6") (pin "6") (pinfunction "SCL_6") (pintype "bidirectional"))
      (node (ref "JP2") (pin "3") (pinfunction "3_3") (pintype "passive"))
      (node (ref "PIN_I2C") (pin "2") (pinfunction "2_2") (pintype "passive"))
    )
    (net (code "67") (name "/SDA") (class "Default")
      (node (ref "IC1") (pin "32") (pinfunction "PA2_32") (pintype "bidirectional"))
      (node (ref "IC2") (pin "27") (pinfunction "SDA_27") (pintype "bidirectional"))
      (node (ref "IC6") (pin "5") (pinfunction "SDA_5") (pintype "bidirectional"))
      (node (ref "JP2") (pin "1") (pinfunction "1_1") (pintype "passive"))
      (node (ref "PIN_I2C") (pin "3") (pinfunction "3_3") (pintype "passive"))
    )
    (net (code "68") (name "/SQW") (class "Default")
      (node (ref "IC6") (pin "7") (pinfunction "SQW/OUT_7") (pintype "bidirectional"))
      (node (ref "R25") (pin "1") (pinfunction "1_1") (pintype "bidirectional"))
      (node (ref "TP1") (pin "TP") (pinfunction "TP_TP") (pintype "input"))
    )
    (net (code "69") (name "/SS") (class "Default")
      (node (ref "IC1") (pin "5") (pinfunction "PA7_5") (pintype "bidirectional"))
      (node (ref "PIN_SPI") (pin "2") (pinfunction "2_2") (pintype "passive"))
    )
    (net (code "70") (name "/SW1") (class "Default")
      (node (ref "IC1") (pin "11") (pinfunction "PD1_11") (pintype "bidirectional"))
      (node (ref "PIN_SWITCH") (pin "1") (pinfunction "1_1") (pintype "passive"))
      (node (ref "SW2") (pin "1") (pinfunction "1_1") (pintype "passive"))
    )
    (net (code "71") (name "/SW2") (class "Default")
      (node (ref "IC1") (pin "12") (pinfunction "PD2_12") (pintype "bidirectional"))
      (node (ref "PIN_SWITCH") (pin "2") (pinfunction "2_2") (pintype "passive"))
      (node (ref "SW2") (pin "2") (pinfunction "2_2") (pintype "passive"))
    )
    (net (code "72") (name "/SW3") (class "Default")
      (node (ref "IC1") (pin "13") (pinfunction "PD3_13") (pintype "bidirectional"))
      (node (ref "PIN_SWITCH") (pin "3") (pinfunction "3_3") (pintype "passive"))
      (node (ref "SW2") (pin "3") (pinfunction "3_3") (pintype "passive"))
    )
    (net (code "73") (name "/SW4") (class "Default")
      (node (ref "IC1") (pin "14") (pinfunction "PD4_14") (pintype "bidirectional"))
      (node (ref "PIN_SWITCH") (pin "4") (pinfunction "4_4") (pintype "passive"))
      (node (ref "SW2") (pin "4") (pinfunction "4_4") (pintype "passive"))
    )
    (net (code "74") (name "/TXD") (class "Default")
      (node (ref "IC1") (pin "20") (pinfunction "PF0_(TOSC1)_20") (pintype "bidirectional"))
      (node (ref "PIN_FTDI") (pin "5") (pinfunction "5_5") (pintype "passive"))
    )
    (net (code "75") (name "/UPDI") (class "Default")
      (node (ref "IC1") (pin "27") (pinfunction "UPDI_27") (pintype "bidirectional"))
      (node (ref "PIN_UPDI") (pin "2") (pinfunction "2_2") (pintype "passive"))
    )
    (net (code "76") (name "/VBAT") (class "Default")
      (node (ref "IC6") (pin "3") (pinfunction "VBAT_3") (pintype "bidirectional"))
      (node (ref "U1") (pin "1") (pinfunction "+_1_1") (pintype "bidirectional"))
      (node (ref "U1") (pin "2") (pinfunction "+_2_2") (pintype "bidirectional"))
    )
    (net (code "77") (name "/VEXT") (class "Default")
      (node (ref "C4") (pin "1") (pinfunction "+_1") (pintype "bidirectional"))
      (node (ref "CON_VEXT") (pin "1") (pinfunction "1_1") (pintype "passive"))
      (node (ref "JP1") (pin "1") (pinfunction "1_1") (pintype "passive"))
    )
    (net (code "78") (name "/VLED") (class "Default")
      (node (ref "C10") (pin "2") (pinfunction "2_2") (pintype "bidirectional"))
      (node (ref "C9") (pin "2") (pinfunction "2_2") (pintype "bidirectional"))
      (node (ref "CON_LED1") (pin "10") (pinfunction "10_10") (pintype "bidirectional"))
      (node (ref "CON_LED1") (pin "12") (pinfunction "12_12") (pintype "bidirectional"))
      (node (ref "CON_LED1") (pin "14") (pinfunction "14_14") (pintype "bidirectional"))
      (node (ref "CON_LED1") (pin "16") (pinfunction "16_16") (pintype "bidirectional"))
      (node (ref "CON_LED1") (pin "2") (pinfunction "2_2") (pintype "bidirectional"))
      (node (ref "CON_LED1") (pin "4") (pinfunction "4_4") (pintype "bidirectional"))
      (node (ref "CON_LED1") (pin "6") (pinfunction "6_6") (pintype "bidirectional"))
      (node (ref "CON_LED1") (pin "8") (pinfunction "8_8") (pintype "bidirectional"))
      (node (ref "CON_LED2") (pin "10") (pinfunction "10_10") (pintype "bidirectional"))
      (node (ref "CON_LED2") (pin "12") (pinfunction "12_12") (pintype "bidirectional"))
      (node (ref "CON_LED2") (pin "14") (pinfunction "14_14") (pintype "bidirectional"))
      (node (ref "CON_LED2") (pin "16") (pinfunction "16_16") (pintype "bidirectional"))
      (node (ref "CON_LED2") (pin "2") (pinfunction "2_2") (pintype "bidirectional"))
      (node (ref "CON_LED2") (pin "4") (pinfunction "4_4") (pintype "bidirectional"))
      (node (ref "CON_LED2") (pin "6") (pinfunction "6_6") (pintype "bidirectional"))
      (node (ref "CON_LED2") (pin "8") (pinfunction "8_8") (pintype "bidirectional"))
      (node (ref "IC3") (pin "10") (pinfunction "COMMON_10") (pintype "bidirectional"))
      (node (ref "IC4") (pin "10") (pinfunction "COMMON_10") (pintype "bidirectional"))
      (node (ref "JP1") (pin "2") (pinfunction "2_2") (pintype "passive"))
      (node (ref "JP1") (pin "4") (pinfunction "4_4") (pintype "passive"))
      (node (ref "JP1") (pin "6") (pinfunction "6_6") (pintype "passive"))
    )
    (net (code "79") (name "/VPWR") (class "Default")
      (node (ref "C1") (pin "2") (pinfunction "2_2") (pintype "bidirectional"))
      (node (ref "CON_VPWR") (pin "1") (pinfunction "1_1") (pintype "passive"))
      (node (ref "D1") (pin "1") (pinfunction "K_1") (pintype "bidirectional"))
      (node (ref "IC5") (pin "1") (pinfunction "IN_1") (pintype "bidirectional"))
      (node (ref "JP1") (pin "5") (pinfunction "5_5") (pintype "passive"))
    )
    (net (code "80") (name "GND") (class "Default")
      (node (ref "C1") (pin "1") (pinfunction "1_1") (pintype "bidirectional"))
      (node (ref "C10") (pin "1") (pinfunction "1_1") (pintype "bidirectional"))
      (node (ref "C11") (pin "1") (pinfunction "1_1") (pintype "bidirectional"))
      (node (ref "C2") (pin "1") (pinfunction "1_1") (pintype "bidirectional"))
      (node (ref "C3") (pin "2") (pinfunction "-_2") (pintype "bidirectional"))
      (node (ref "C4") (pin "2") (pinfunction "-_2") (pintype "bidirectional"))
      (node (ref "C6") (pin "1") (pinfunction "1_1") (pintype "bidirectional"))
      (node (ref "C7") (pin "1") (pinfunction "1_1") (pintype "bidirectional"))
      (node (ref "C8") (pin "1") (pinfunction "1_1") (pintype "bidirectional"))
      (node (ref "C9") (pin "1") (pinfunction "1_1") (pintype "bidirectional"))
      (node (ref "CON_BR") (pin "3") (pinfunction "3_3") (pintype "passive"))
      (node (ref "CON_IRDA") (pin "3") (pinfunction "3_3") (pintype "passive"))
      (node (ref "CON_VEXT") (pin "2") (pinfunction "2_2") (pintype "passive"))
      (node (ref "CON_VPWR") (pin "2") (pinfunction "2_2") (pintype "passive"))
      (node (ref "IC1") (pin "19") (pinfunction "GND_1_19") (pintype "bidirectional"))
      (node (ref "IC1") (pin "29") (pinfunction "GND_2_29") (pintype "bidirectional"))
      (node (ref "IC2") (pin "14") (pinfunction "VSS_14") (pintype "bidirectional"))
      (node (ref "IC3") (pin "9") (pinfunction "GND_9") (pintype "bidirectional"))
      (node (ref "IC4") (pin "9") (pinfunction "GND_9") (pintype "bidirectional"))
      (node (ref "IC5") (pin "2") (pinfunction "GND_2") (pintype "bidirectional"))
      (node (ref "IC6") (pin "4") (pinfunction "GND_4") (pintype "bidirectional"))
      (node (ref "LED1") (pin "-") (pinfunction "-_-") (pintype "passive"))
      (node (ref "LED2") (pin "3") (pinfunction "VSS_3") (pintype "power_in"))
      (node (ref "PIN_ANA1") (pin "3") (pinfunction "3_3") (pintype "passive"))
      (node (ref "PIN_ANA2") (pin "7") (pinfunction "7_7") (pintype "passive"))
      (node (ref "PIN_DIGITAL") (pin "7") (pinfunction "7_7") (pintype "passive"))
      (node (ref "PIN_FTDI") (pin "1") (pinfunction "1_1") (pintype "passive"))
      (node (ref "PIN_I2C") (pin "4") (pinfunction "4_4") (pintype "passive"))
      (node (ref "PIN_LED") (pin "3") (pinfunction "3_3") (pintype "passive"))
      (node (ref "PIN_SPI") (pin "6") (pinfunction "6_6") (pintype "passive"))
      (node (ref "PIN_SWITCH") (pin "5") (pinfunction "5_5") (pintype "passive"))
      (node (ref "PIN_UPDI") (pin "3") (pinfunction "3_3") (pintype "passive"))
      (node (ref "R10") (pin "1") (pinfunction "1_1") (pintype "bidirectional"))
      (node (ref "R11") (pin "1") (pinfunction "1_1") (pintype "bidirectional"))
      (node (ref "R12") (pin "1") (pinfunction "1_1") (pintype "bidirectional"))
      (node (ref "R13") (pin "1") (pinfunction "1_1") (pintype "bidirectional"))
      (node (ref "R14") (pin "1") (pinfunction "1_1") (pintype "bidirectional"))
      (node (ref "R15") (pin "1") (pinfunction "1_1") (pintype "bidirectional"))
      (node (ref "R16") (pin "1") (pinfunction "1_1") (pintype "bidirectional"))
      (node (ref "R17") (pin "1") (pinfunction "1_1") (pintype "bidirectional"))
      (node (ref "R18") (pin "1") (pinfunction "1_1") (pintype "bidirectional"))
      (node (ref "R19") (pin "1") (pinfunction "1_1") (pintype "bidirectional"))
      (node (ref "R20") (pin "1") (pinfunction "1_1") (pintype "bidirectional"))
      (node (ref "R21") (pin "1") (pinfunction "1_1") (pintype "bidirectional"))
      (node (ref "R22") (pin "1") (pinfunction "1_1") (pintype "bidirectional"))
      (node (ref "R23") (pin "1") (pinfunction "1_1") (pintype "bidirectional"))
      (node (ref "R24") (pin "1") (pinfunction "1_1") (pintype "bidirectional"))
      (node (ref "R5") (pin "1") (pinfunction "1_1") (pintype "bidirectional"))
      (node (ref "R6") (pin "1") (pinfunction "1_1") (pintype "bidirectional"))
      (node (ref "R7") (pin "1") (pinfunction "1_1") (pintype "bidirectional"))
      (node (ref "R8") (pin "1") (pinfunction "1_1") (pintype "bidirectional"))
      (node (ref "R9") (pin "1") (pinfunction "1_1") (pintype "bidirectional"))
      (node (ref "SW1") (pin "3") (pinfunction "3_3") (pintype "bidirectional"))
      (node (ref "SW1") (pin "4") (pinfunction "4_4") (pintype "bidirectional"))
      (node (ref "SW2") (pin "5") (pinfunction "5_5") (pintype "passive"))
      (node (ref "SW2") (pin "6") (pinfunction "6_6") (pintype "passive"))
      (node (ref "SW2") (pin "7") (pinfunction "7_7") (pintype "passive"))
      (node (ref "SW2") (pin "8") (pinfunction "8_8") (pintype "passive"))
      (node (ref "U1") (pin "3") (pinfunction "-_3") (pintype "bidirectional"))
    )
    (net (code "81") (name "Net-(JP2-Pad2)") (class "Default")
      (node (ref "JP2") (pin "2") (pinfunction "2_2") (pintype "passive"))
      (node (ref "R3") (pin "1") (pinfunction "1_1") (pintype "bidirectional"))
    )
    (net (code "82") (name "Net-(JP2-Pad4)") (class "Default")
      (node (ref "JP2") (pin "4") (pinfunction "4_4") (pintype "passive"))
      (node (ref "R4") (pin "1") (pinfunction "1_1") (pintype "bidirectional"))
    )
    (net (code "83") (name "Net-(LED1-Pad+)") (class "Default")
      (node (ref "LED1") (pin "+") (pinfunction "+_+") (pintype "passive"))
      (node (ref "R1") (pin "1") (pinfunction "1_1") (pintype "bidirectional"))
    )
  )
)
